# rfDuinoBO.net
KiCad netlist of a schematic drawn in EAGLE
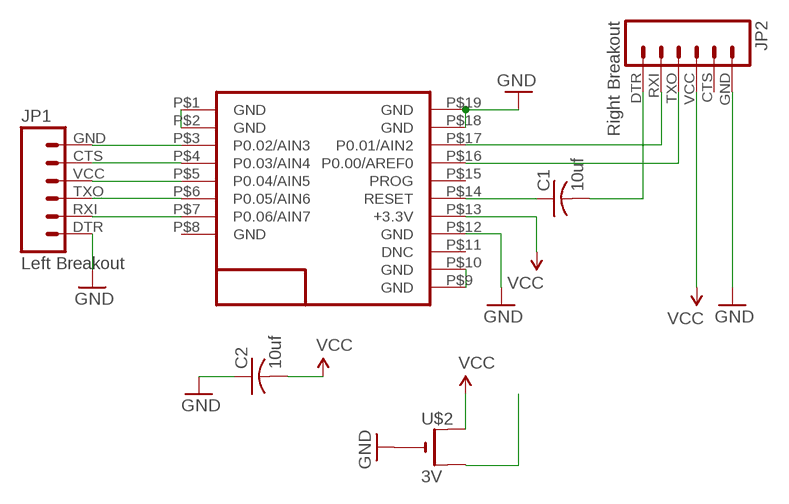
[diagram p0: schematic, sheet 1]

(export (version "E")
  (design (tool "Eeschema 10.0.6"))
  (components
    (comp (ref "C1")
      (value "10uf")
      (footprint "eagle-import:C0603")
      (libsource (lib "eagle-import") (part "C-USC0603"))
    )
    (comp (ref "C2")
      (value "10uf")
      (footprint "eagle-import:C0603")
      (libsource (lib "eagle-import") (part "C-USC0603"))
    )
    (comp (ref "JP1")
      (value "Left Breakout")
      (footprint "eagle-import:1X06")
      (libsource (lib "eagle-import") (part "M06SIP"))
    )
    (comp (ref "JP2")
      (value "Right Breakout")
      (footprint "eagle-import:1X06")
      (libsource (lib "eagle-import") (part "M06SIP"))
    )
    (comp (ref "U$1")
      (value "RFD22301")
      (footprint "eagle-import:RFD21733")
      (libsource (lib "eagle-import") (part "RFD22301"))
    )
    (comp (ref "U$2")
      (value "3V")
      (footprint "eagle-import:CR2032-THRU")
      (libsource (lib "eagle-import") (part "CR2032THM"))
    )
  )
  (nets
    (net (code "1") (name "GND") (class "Default")
      (node (ref "C2") (pin "1") (pinfunction "1_1") (pintype "passive"))
      (node (ref "JP1") (pin "DTR") (pinfunction "1_DTR") (pintype "passive"))
      (node (ref "JP2") (pin "GND") (pinfunction "6_GND") (pintype "passive"))
      (node (ref "U$1") (pin "P$12") (pinfunction "GND_P$12") (pintype "bidirectional"))
      (node (ref "U$1") (pin "P$18") (pinfunction "GND_P$18") (pintype "bidirectional"))
      (node (ref "U$1") (pin "P$19") (pinfunction "GND_P$19") (pintype "bidirectional"))
      (node (ref "U$2") (pin "-") (pinfunction "-_-") (pintype "passive"))
    )
    (net (code "2") (name "Net-(JP1-2)") (class "Default")
      (node (ref "JP1") (pin "RXI") (pinfunction "2_RXI") (pintype "passive"))
      (node (ref "U$1") (pin "P$7") (pinfunction "P0.06/AIN7_P$7") (pintype "bidirectional"))
    )
    (net (code "3") (name "Net-(JP1-3)") (class "Default")
      (node (ref "JP1") (pin "TXO") (pinfunction "3_TXO") (pintype "passive"))
      (node (ref "U$1") (pin "P$6") (pinfunction "P0.05/AIN6_P$6") (pintype "bidirectional"))
    )
    (net (code "4") (name "Net-(JP1-4)") (class "Default")
      (node (ref "JP1") (pin "VCC") (pinfunction "4_VCC") (pintype "passive"))
      (node (ref "U$1") (pin "P$5") (pinfunction "P0.04/AIN5_P$5") (pintype "bidirectional"))
    )
    (net (code "5") (name "Net-(JP1-5)") (class "Default")
      (node (ref "JP1") (pin "CTS") (pinfunction "5_CTS") (pintype "passive"))
      (node (ref "U$1") (pin "P$4") (pinfunction "P0.03/AIN4_P$4") (pintype "bidirectional"))
    )
    (net (code "6") (name "Net-(JP1-6)") (class "Default")
      (node (ref "JP1") (pin "GND") (pinfunction "6_GND") (pintype "passive"))
      (node (ref "U$1") (pin "P$3") (pinfunction "P0.02/AIN3_P$3") (pintype "bidirectional"))
    )
    (net (code "7") (name "Net-(JP2-1)") (class "Default")
      (node (ref "C1") (pin "2") (pinfunction "2_2") (pintype "passive"))
      (node (ref "JP2") (pin "DTR") (pinfunction "1_DTR") (pintype "passive"))
    )
    (net (code "8") (name "Net-(JP2-2)") (class "Default")
      (node (ref "JP2") (pin "RXI") (pinfunction "2_RXI") (pintype "passive"))
      (node (ref "U$1") (pin "P$17") (pinfunction "P0.01/AIN2_P$17") (pintype "bidirectional"))
    )
    (net (code "9") (name "Net-(JP2-3)") (class "Default")
      (node (ref "JP2") (pin "TXO") (pinfunction "3_TXO") (pintype "passive"))
      (node (ref "U$1") (pin "P$16") (pinfunction "P0.00/AREF0_P$16") (pintype "bidirectional"))
    )
    (net (code "10") (name "Net-(U$1-GND-PadP$1)") (class "Default")
      (node (ref "U$1") (pin "P$1") (pinfunction "GND_P$1") (pintype "bidirectional"))
      (node (ref "U$1") (pin "P$2") (pinfunction "GND_P$2") (pintype "bidirectional"))
    )
    (net (code "11") (name "Net-(U$1-GND-PadP$10)") (class "Default")
      (node (ref "U$1") (pin "P$10") (pinfunction "GND_P$10") (pintype "bidirectional"))
      (node (ref "U$1") (pin "P$9") (pinfunction "GND_P$9") (pintype "bidirectional"))
    )
    (net (code "12") (name "Net-(U$1-RESET)") (class "Default")
      (node (ref "C1") (pin "1") (pinfunction "1_1") (pintype "passive"))
      (node (ref "U$1") (pin "P$14") (pinfunction "RESET_P$14") (pintype "bidirectional"))
    )
    (net (code "13") (name "VCC") (class "Default")
      (node (ref "C2") (pin "2") (pinfunction "2_2") (pintype "passive"))
      (node (ref "JP2") (pin "VCC") (pinfunction "4_VCC") (pintype "passive"))
      (node (ref "U$1") (pin "P$13") (pinfunction "+3.3V_P$13") (pintype "bidirectional"))
      (node (ref "U$2") (pin "+1") (pinfunction "+_+1") (pintype "passive"))
    )
    (net (code "14") (name "unconnected-(JP2-5-PadCTS)") (class "Default")
      (node (ref "JP2") (pin "CTS") (pinfunction "5_CTS") (pintype "passive"))
    )
    (net (code "15") (name "unconnected-(U$1-DNC-PadP$11)") (class "Default")
      (node (ref "U$1") (pin "P$11") (pinfunction "DNC_P$11") (pintype "bidirectional"))
    )
    (net (code "16") (name "unconnected-(U$1-GND-PadP$8)") (class "Default")
      (node (ref "U$1") (pin "P$8") (pinfunction "GND_P$8") (pintype "bidirectional"))
    )
    (net (code "17") (name "unconnected-(U$1-PROG-PadP$15)") (class "Default")
      (node (ref "U$1") (pin "P$15") (pinfunction "PROG_P$15") (pintype "bidirectional"))
    )
    (net (code "18") (name "unconnected-(U$2-+1-Pad+2)") (class "Default")
      (node (ref "U$2") (pin "+2") (pinfunction "+1_+2") (pintype "passive"))
    )
  )
)
